# V4-AddOnRaspiUART-V002.net
KiCad netlist of a schematic drawn in EAGLE
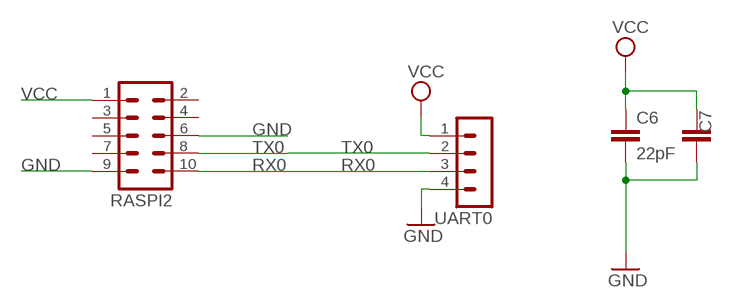
[diagram p0: schematic, sheet 1]

(export (version "E")
  (design (tool "Eeschema 10.0.6"))
  (components
    (comp (ref "C6")
      (value "22pF")
      (footprint "eagle-import:C0805")
      (libsource (lib "eagle-import") (part "C-EUC0805"))
    )
    (comp (ref "C7")
      (value "C-EUC1812")
      (footprint "eagle-import:C1812")
      (libsource (lib "eagle-import") (part "C-EUC1812"))
    )
    (comp (ref "RASPI2")
      (value "MA05-2")
      (footprint "eagle-import:MA05-2")
      (libsource (lib "eagle-import") (part "MA05-2"))
    )
    (comp (ref "UART0")
      (value "MA04-1")
      (footprint "eagle-import:MA04-1")
      (libsource (lib "eagle-import") (part "MA04-1"))
    )
  )
  (nets
    (net (code "1") (name "/RX0") (class "Default")
      (node (ref "RASPI2") (pin "10") (pinfunction "10_10") (pintype "passive"))
      (node (ref "UART0") (pin "3") (pinfunction "3_3") (pintype "passive"))
    )
    (net (code "2") (name "/TX0") (class "Default")
      (node (ref "RASPI2") (pin "8") (pinfunction "8_8") (pintype "passive"))
      (node (ref "UART0") (pin "2") (pinfunction "2_2") (pintype "passive"))
    )
    (net (code "3") (name "GND") (class "Default")
      (node (ref "C6") (pin "2") (pinfunction "2_2") (pintype "passive"))
      (node (ref "C7") (pin "1") (pinfunction "1_1") (pintype "passive"))
      (node (ref "RASPI2") (pin "6") (pinfunction "6_6") (pintype "passive"))
      (node (ref "RASPI2") (pin "9") (pinfunction "9_9") (pintype "passive"))
      (node (ref "UART0") (pin "4") (pinfunction "4_4") (pintype "passive"))
    )
    (net (code "4") (name "VCC") (class "Default")
      (node (ref "C6") (pin "1") (pinfunction "1_1") (pintype "passive"))
      (node (ref "C7") (pin "2") (pinfunction "2_2") (pintype "passive"))
      (node (ref "RASPI2") (pin "1") (pinfunction "1_1") (pintype "passive"))
      (node (ref "UART0") (pin "1") (pinfunction "1_1") (pintype "passive"))
    )
    (net (code "5") (name "unconnected-(RASPI2-Pad2)") (class "Default")
      (node (ref "RASPI2") (pin "2") (pinfunction "2_2") (pintype "passive"))
    )
    (net (code "6") (name "unconnected-(RASPI2-Pad3)") (class "Default")
      (node (ref "RASPI2") (pin "3") (pinfunction "3_3") (pintype "passive"))
    )
    (net (code "7") (name "unconnected-(RASPI2-Pad4)") (class "Default")
      (node (ref "RASPI2") (pin "4") (pinfunction "4_4") (pintype "passive"))
    )
    (net (code "8") (name "unconnected-(RASPI2-Pad5)") (class "Default")
      (node (ref "RASPI2") (pin "5") (pinfunction "5_5") (pintype "passive"))
    )
    (net (code "9") (name "unconnected-(RASPI2-Pad7)") (class "Default")
      (node (ref "RASPI2") (pin "7") (pinfunction "7_7") (pintype "passive"))
    )
  )
)
